# ProDuino-v2.net
KiCad netlist of a schematic drawn in EAGLE
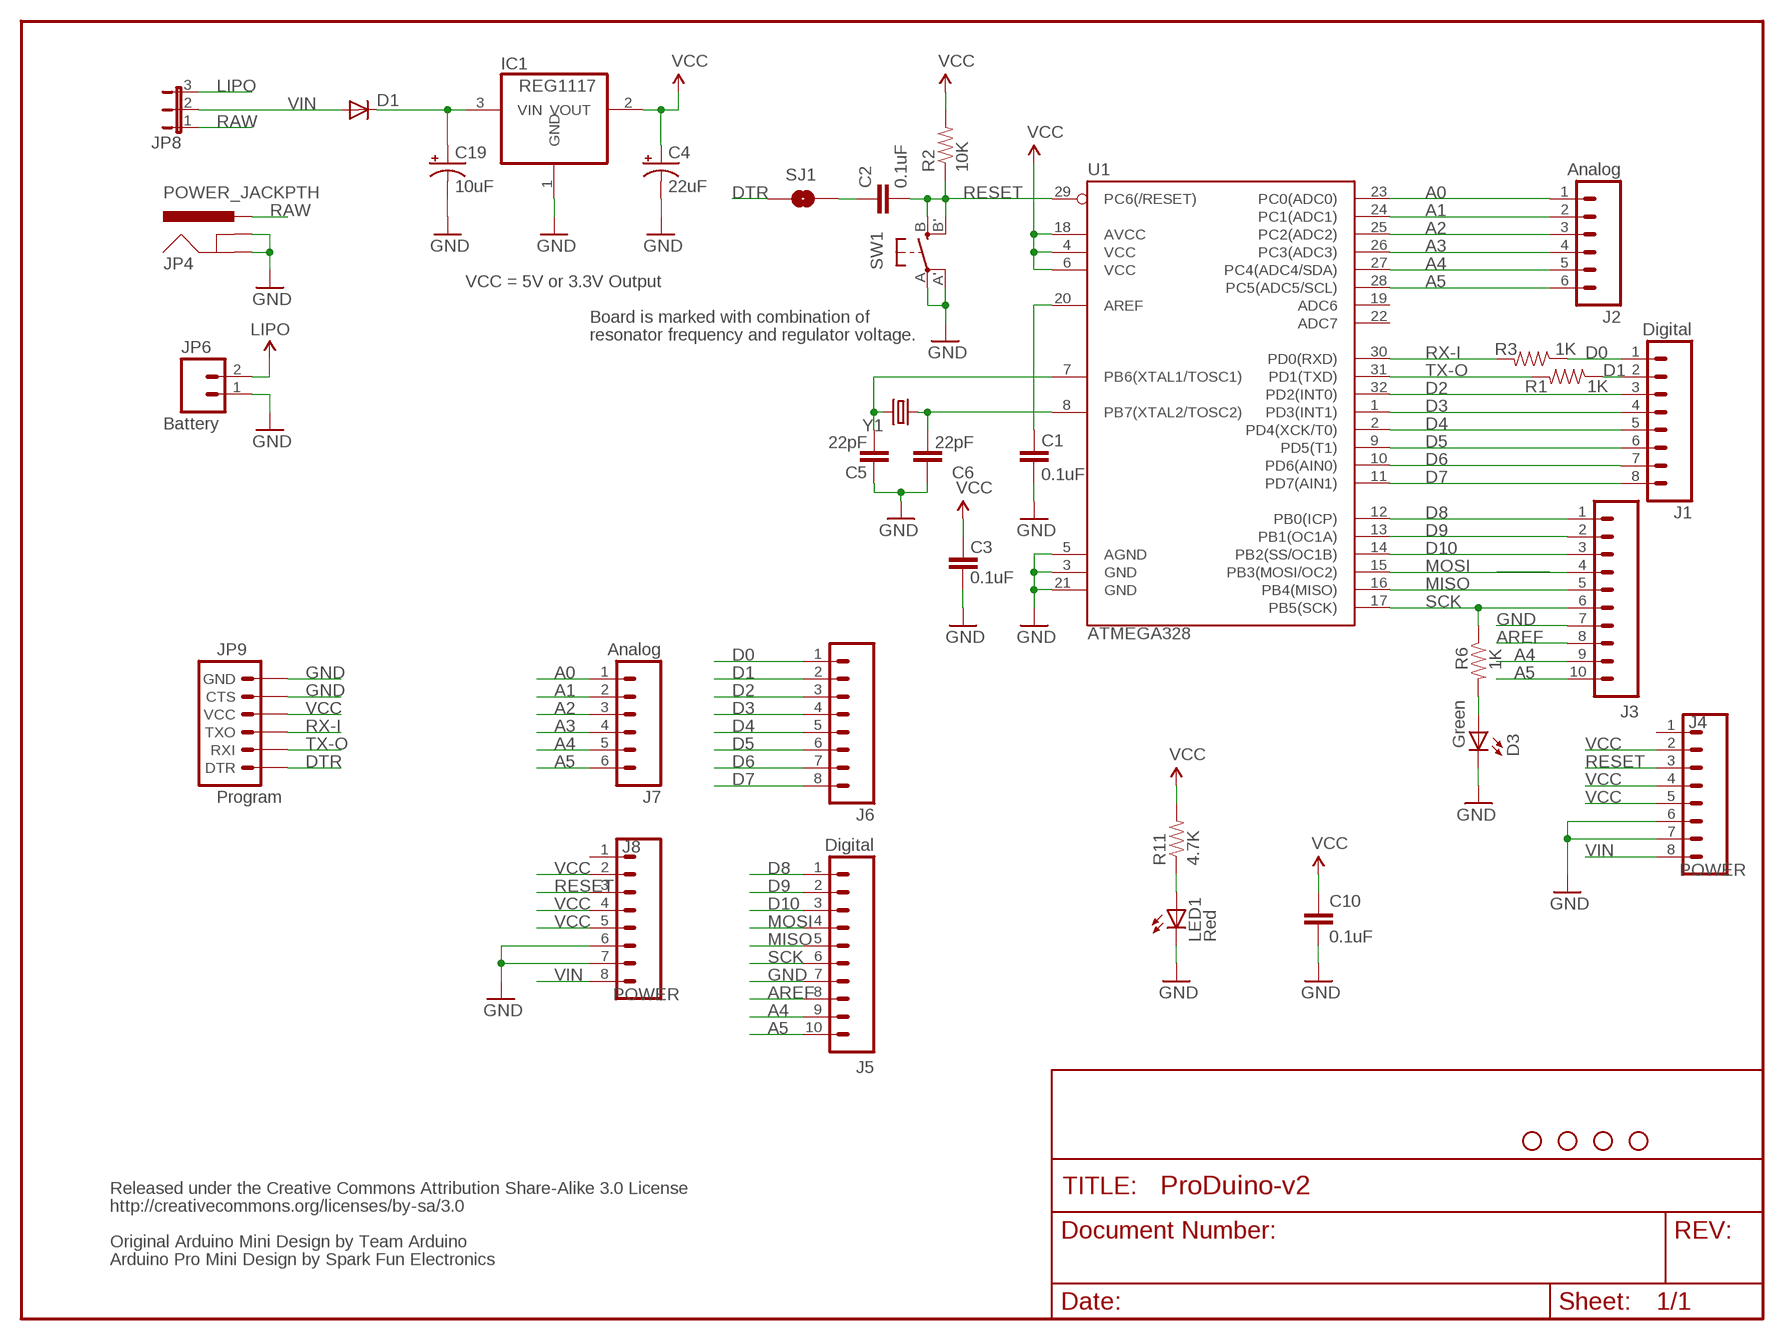
[diagram p0: schematic, sheet 1]

(export (version "E")
  (design (tool "Eeschema 10.0.6"))
  (components
    (comp (ref "C1")
      (value "0.1uF")
      (footprint "eagle-import:0603-CAP")
      (libsource (lib "eagle-import") (part "CAP0603-CAP"))
    )
    (comp (ref "C2")
      (value "0.1uF")
      (footprint "eagle-import:0603-CAP")
      (libsource (lib "eagle-import") (part "CAP0603-CAP"))
    )
    (comp (ref "C3")
      (value "0.1uF")
      (footprint "eagle-import:0603-CAP")
      (libsource (lib "eagle-import") (part "CAP0603-CAP"))
    )
    (comp (ref "C4")
      (value "22uF")
      (footprint "eagle-import:EIA3216")
      (libsource (lib "eagle-import") (part "CAP_POL1206"))
    )
    (comp (ref "C5")
      (value "22pF")
      (footprint "eagle-import:0603-CAP")
      (libsource (lib "eagle-import") (part "CAP0603-CAP"))
    )
    (comp (ref "C6")
      (value "22pF")
      (footprint "eagle-import:0603-CAP")
      (libsource (lib "eagle-import") (part "CAP0603-CAP"))
    )
    (comp (ref "C10")
      (value "0.1uF")
      (footprint "eagle-import:0603-CAP")
      (libsource (lib "eagle-import") (part "CAP0603-CAP"))
    )
    (comp (ref "C19")
      (value "10uF")
      (footprint "eagle-import:EIA3216")
      (libsource (lib "eagle-import") (part "CAP_POL1206"))
    )
    (comp (ref "D1")
      (value "DIODESMA")
      (footprint "eagle-import:SMA-DIODE")
      (libsource (lib "eagle-import") (part "DIODESMA"))
    )
    (comp (ref "D3")
      (value "Green")
      (footprint "eagle-import:LED-0603")
      (libsource (lib "eagle-import") (part "LED0603"))
    )
    (comp (ref "IC1")
      (value "REG1117")
      (footprint "eagle-import:SOT223")
      (libsource (lib "eagle-import") (part "REG1117"))
    )
    (comp (ref "J1")
      (value "Digital")
      (footprint "eagle-import:1X08")
      (libsource (lib "eagle-import") (part "M081X08"))
    )
    (comp (ref "J2")
      (value "Analog")
      (footprint "eagle-import:1X06")
      (libsource (lib "eagle-import") (part "M06SIP"))
    )
    (comp (ref "J3")
      (value "M10\"")
      (footprint "eagle-import:1X10")
      (libsource (lib "eagle-import") (part "M10{dblquote}"))
    )
    (comp (ref "J4")
      (value "POWER")
      (footprint "eagle-import:1X08")
      (libsource (lib "eagle-import") (part "SparkFun-Connectors_M081X08"))
    )
    (comp (ref "J5")
      (value "Digital")
      (footprint "eagle-import:1X10")
      (libsource (lib "eagle-import") (part "M10{dblquote}"))
    )
    (comp (ref "J6")
      (value "M081X08")
      (footprint "eagle-import:1X08")
      (libsource (lib "eagle-import") (part "M081X08"))
    )
    (comp (ref "J7")
      (value "Analog")
      (footprint "eagle-import:1X06")
      (libsource (lib "eagle-import") (part "M06SIP"))
    )
    (comp (ref "J8")
      (value "POWER")
      (footprint "eagle-import:1X08")
      (libsource (lib "eagle-import") (part "SparkFun-Connectors_M081X08"))
    )
    (comp (ref "JP4")
      (value "POWER_JACKPTH")
      (footprint "eagle-import:POWER_JACK_PTH")
      (libsource (lib "eagle-import") (part "POWER_JACKPTH"))
    )
    (comp (ref "JP6")
      (value "Battery")
      (footprint "eagle-import:1X02")
      (libsource (lib "eagle-import") (part "M02PTH"))
    )
    (comp (ref "JP8")
      (value "JP2E")
      (footprint "eagle-import:JP2")
      (libsource (lib "eagle-import") (part "JP2E"))
    )
    (comp (ref "JP9")
      (value "Program")
      (footprint "eagle-import:1X06")
      (libsource (lib "eagle-import") (part "ARDUINO_SERIAL_PROGRAMPTH"))
    )
    (comp (ref "LED1")
      (value "Red")
      (footprint "eagle-import:LED-0603")
      (libsource (lib "eagle-import") (part "LED0603"))
    )
    (comp (ref "R1")
      (value "1K")
      (footprint "eagle-import:0603-RES")
      (libsource (lib "eagle-import") (part "RESISTOR0603-RES"))
    )
    (comp (ref "R2")
      (value "10K")
      (footprint "eagle-import:0603-RES")
      (libsource (lib "eagle-import") (part "RESISTOR0603-RES"))
    )
    (comp (ref "R3")
      (value "1K")
      (footprint "eagle-import:0603-RES")
      (libsource (lib "eagle-import") (part "RESISTOR0603-RES"))
    )
    (comp (ref "R6")
      (value "1K")
      (footprint "eagle-import:0603-RES")
      (libsource (lib "eagle-import") (part "RESISTOR0603-RES"))
    )
    (comp (ref "R11")
      (value "4.7K")
      (footprint "eagle-import:0603-RES")
      (libsource (lib "eagle-import") (part "RESISTOR0603-RES"))
    )
    (comp (ref "SJ1")
      (value "SOLDERJUMPERNC3")
      (footprint "eagle-import:SJ_2S-NOTRACE")
      (libsource (lib "eagle-import") (part "SOLDERJUMPERNC2"))
    )
    (comp (ref "SW1")
      (value "SPST_TACT-EVQQ2")
      (footprint "eagle-import:EVQ-Q2")
      (libsource (lib "eagle-import") (part "SPST_TACT-EVQQ2"))
    )
    (comp (ref "U$1")
      (value "STAND-OFF")
      (footprint "eagle-import:STAND-OFF")
      (libsource (lib "eagle-import") (part "STAND-OFF"))
    )
    (comp (ref "U$3")
      (value "STAND-OFF")
      (footprint "eagle-import:STAND-OFF")
      (libsource (lib "eagle-import") (part "STAND-OFF"))
    )
    (comp (ref "U$9")
      (value "STAND-OFF")
      (footprint "eagle-import:STAND-OFF")
      (libsource (lib "eagle-import") (part "STAND-OFF"))
    )
    (comp (ref "U$10")
      (value "STAND-OFF")
      (footprint "eagle-import:STAND-OFF")
      (libsource (lib "eagle-import") (part "STAND-OFF"))
    )
    (comp (ref "U1")
      (value "ATMEGA328")
      (footprint "eagle-import:TQFP32-08")
      (libsource (lib "eagle-import") (part "ATMEGA168"))
    )
    (comp (ref "Y1")
      (value "CRYSTAL5X3")
      (footprint "eagle-import:CRYSTAL-SMD-5X3")
      (libsource (lib "eagle-import") (part "CRYSTAL5X3"))
    )
  )
  (nets
    (net (code "1") (name "/A0") (class "Default")
      (node (ref "J2") (pin "1") (pinfunction "1_1") (pintype "passive"))
      (node (ref "J7") (pin "1") (pinfunction "1_1") (pintype "passive"))
      (node (ref "U1") (pin "23") (pinfunction "PC0(ADC0)_23") (pintype "bidirectional"))
    )
    (net (code "2") (name "/A1") (class "Default")
      (node (ref "J2") (pin "2") (pinfunction "2_2") (pintype "passive"))
      (node (ref "J7") (pin "2") (pinfunction "2_2") (pintype "passive"))
      (node (ref "U1") (pin "24") (pinfunction "PC1(ADC1)_24") (pintype "bidirectional"))
    )
    (net (code "3") (name "/A2") (class "Default")
      (node (ref "J2") (pin "3") (pinfunction "3_3") (pintype "passive"))
      (node (ref "J7") (pin "3") (pinfunction "3_3") (pintype "passive"))
      (node (ref "U1") (pin "25") (pinfunction "PC2(ADC2)_25") (pintype "bidirectional"))
    )
    (net (code "4") (name "/A3") (class "Default")
      (node (ref "J2") (pin "4") (pinfunction "4_4") (pintype "passive"))
      (node (ref "J7") (pin "4") (pinfunction "4_4") (pintype "passive"))
      (node (ref "U1") (pin "26") (pinfunction "PC3(ADC3)_26") (pintype "bidirectional"))
    )
    (net (code "5") (name "/A4") (class "Default")
      (node (ref "J2") (pin "5") (pinfunction "5_5") (pintype "passive"))
      (node (ref "J3") (pin "9") (pinfunction "9_9") (pintype "passive"))
      (node (ref "J5") (pin "9") (pinfunction "9_9") (pintype "passive"))
      (node (ref "J7") (pin "5") (pinfunction "5_5") (pintype "passive"))
      (node (ref "U1") (pin "27") (pinfunction "PC4(ADC4/SDA)_27") (pintype "bidirectional"))
    )
    (net (code "6") (name "/A5") (class "Default")
      (node (ref "J2") (pin "6") (pinfunction "6_6") (pintype "passive"))
      (node (ref "J3") (pin "10") (pinfunction "10_10") (pintype "passive"))
      (node (ref "J5") (pin "10") (pinfunction "10_10") (pintype "passive"))
      (node (ref "J7") (pin "6") (pinfunction "6_6") (pintype "passive"))
      (node (ref "U1") (pin "28") (pinfunction "PC5(ADC5/SCL)_28") (pintype "bidirectional"))
    )
    (net (code "7") (name "/AREF") (class "Default")
      (node (ref "C1") (pin "2") (pinfunction "2_2") (pintype "passive"))
      (node (ref "J3") (pin "8") (pinfunction "8_8") (pintype "passive"))
      (node (ref "J5") (pin "8") (pinfunction "8_8") (pintype "passive"))
      (node (ref "U1") (pin "20") (pinfunction "AREF_20") (pintype "bidirectional"))
    )
    (net (code "8") (name "/D0") (class "Default")
      (node (ref "J1") (pin "1") (pinfunction "1_1") (pintype "passive"))
      (node (ref "J6") (pin "1") (pinfunction "1_1") (pintype "passive"))
      (node (ref "R3") (pin "1") (pinfunction "1_1") (pintype "passive"))
    )
    (net (code "9") (name "/D1") (class "Default")
      (node (ref "J1") (pin "2") (pinfunction "2_2") (pintype "passive"))
      (node (ref "J6") (pin "2") (pinfunction "2_2") (pintype "passive"))
      (node (ref "R1") (pin "1") (pinfunction "1_1") (pintype "passive"))
    )
    (net (code "10") (name "/D2") (class "Default")
      (node (ref "J1") (pin "3") (pinfunction "3_3") (pintype "passive"))
      (node (ref "J6") (pin "3") (pinfunction "3_3") (pintype "passive"))
      (node (ref "U1") (pin "32") (pinfunction "PD2(INT0)_32") (pintype "bidirectional"))
    )
    (net (code "11") (name "/D3") (class "Default")
      (node (ref "J1") (pin "4") (pinfunction "4_4") (pintype "passive"))
      (node (ref "J6") (pin "4") (pinfunction "4_4") (pintype "passive"))
      (node (ref "U1") (pin "1") (pinfunction "PD3(INT1)_1") (pintype "bidirectional"))
    )
    (net (code "12") (name "/D4") (class "Default")
      (node (ref "J1") (pin "5") (pinfunction "5_5") (pintype "passive"))
      (node (ref "J6") (pin "5") (pinfunction "5_5") (pintype "passive"))
      (node (ref "U1") (pin "2") (pinfunction "PD4(XCK/T0)_2") (pintype "bidirectional"))
    )
    (net (code "13") (name "/D5") (class "Default")
      (node (ref "J1") (pin "6") (pinfunction "6_6") (pintype "passive"))
      (node (ref "J6") (pin "6") (pinfunction "6_6") (pintype "passive"))
      (node (ref "U1") (pin "9") (pinfunction "PD5(T1)_9") (pintype "bidirectional"))
    )
    (net (code "14") (name "/D6") (class "Default")
      (node (ref "J1") (pin "7") (pinfunction "7_7") (pintype "passive"))
      (node (ref "J6") (pin "7") (pinfunction "7_7") (pintype "passive"))
      (node (ref "U1") (pin "10") (pinfunction "PD6(AIN0)_10") (pintype "bidirectional"))
    )
    (net (code "15") (name "/D7") (class "Default")
      (node (ref "J1") (pin "8") (pinfunction "8_8") (pintype "passive"))
      (node (ref "J6") (pin "8") (pinfunction "8_8") (pintype "passive"))
      (node (ref "U1") (pin "11") (pinfunction "PD7(AIN1)_11") (pintype "bidirectional"))
    )
    (net (code "16") (name "/D8") (class "Default")
      (node (ref "J3") (pin "1") (pinfunction "1_1") (pintype "passive"))
      (node (ref "J5") (pin "1") (pinfunction "1_1") (pintype "passive"))
      (node (ref "U1") (pin "12") (pinfunction "PB0(ICP)_12") (pintype "bidirectional"))
    )
    (net (code "17") (name "/D9") (class "Default")
      (node (ref "J3") (pin "2") (pinfunction "2_2") (pintype "passive"))
      (node (ref "J5") (pin "2") (pinfunction "2_2") (pintype "passive"))
      (node (ref "U1") (pin "13") (pinfunction "PB1(OC1A)_13") (pintype "bidirectional"))
    )
    (net (code "18") (name "/D10") (class "Default")
      (node (ref "J3") (pin "3") (pinfunction "3_3") (pintype "passive"))
      (node (ref "J5") (pin "3") (pinfunction "3_3") (pintype "passive"))
      (node (ref "U1") (pin "14") (pinfunction "PB2(SS/OC1B)_14") (pintype "bidirectional"))
    )
    (net (code "19") (name "/DTR") (class "Default")
      (node (ref "JP9") (pin "1") (pinfunction "DTR_1") (pintype "passive"))
      (node (ref "SJ1") (pin "1") (pinfunction "1_1") (pintype "passive"))
    )
    (net (code "20") (name "/MISO") (class "Default")
      (node (ref "J3") (pin "5") (pinfunction "5_5") (pintype "passive"))
      (node (ref "J5") (pin "5") (pinfunction "5_5") (pintype "passive"))
      (node (ref "U1") (pin "16") (pinfunction "PB4(MISO)_16") (pintype "bidirectional"))
    )
    (net (code "21") (name "/MOSI") (class "Default")
      (node (ref "J3") (pin "4") (pinfunction "4_4") (pintype "passive"))
      (node (ref "J5") (pin "4") (pinfunction "4_4") (pintype "passive"))
      (node (ref "U1") (pin "15") (pinfunction "PB3(MOSI/OC2)_15") (pintype "bidirectional"))
    )
    (net (code "22") (name "/RAW") (class "Default")
      (node (ref "JP4") (pin "PWR") (pinfunction "PWR_PWR") (pintype "bidirectional"))
      (node (ref "JP8") (pin "1") (pinfunction "1_1") (pintype "passive"))
    )
    (net (code "23") (name "/RESET") (class "Default")
      (node (ref "C2") (pin "2") (pinfunction "2_2") (pintype "passive"))
      (node (ref "J4") (pin "3") (pinfunction "3_3") (pintype "passive"))
      (node (ref "J8") (pin "3") (pinfunction "3_3") (pintype "passive"))
      (node (ref "R2") (pin "1") (pinfunction "1_1") (pintype "passive"))
      (node (ref "SW1") (pin "B") (pinfunction "S_B") (pintype "passive"))
      (node (ref "SW1") (pin "B'") (pinfunction "S1_B'") (pintype "passive"))
      (node (ref "U1") (pin "29") (pinfunction "PC6(/RESET)_29") (pintype "bidirectional"))
    )
    (net (code "24") (name "/RX-I") (class "Default")
      (node (ref "JP9") (pin "3") (pinfunction "TXO_3") (pintype "passive"))
      (node (ref "R3") (pin "2") (pinfunction "2_2") (pintype "passive"))
      (node (ref "U1") (pin "30") (pinfunction "PD0(RXD)_30") (pintype "bidirectional"))
    )
    (net (code "25") (name "/SCK") (class "Default")
      (node (ref "J3") (pin "6") (pinfunction "6_6") (pintype "passive"))
      (node (ref "J5") (pin "6") (pinfunction "6_6") (pintype "passive"))
      (node (ref "R6") (pin "1") (pinfunction "1_1") (pintype "passive"))
      (node (ref "U1") (pin "17") (pinfunction "PB5(SCK)_17") (pintype "bidirectional"))
    )
    (net (code "26") (name "/TX-O") (class "Default")
      (node (ref "JP9") (pin "2") (pinfunction "RXI_2") (pintype "passive"))
      (node (ref "R1") (pin "2") (pinfunction "2_2") (pintype "passive"))
      (node (ref "U1") (pin "31") (pinfunction "PD1(TXD)_31") (pintype "bidirectional"))
    )
    (net (code "27") (name "/VIN") (class "Default")
      (node (ref "D1") (pin "A") (pinfunction "A_A") (pintype "passive"))
      (node (ref "J4") (pin "8") (pinfunction "8_8") (pintype "passive"))
      (node (ref "J8") (pin "8") (pinfunction "8_8") (pintype "passive"))
      (node (ref "JP8") (pin "2") (pinfunction "2_2") (pintype "passive"))
    )
    (net (code "28") (name "GND") (class "Default")
      (node (ref "C1") (pin "1") (pinfunction "1_1") (pintype "passive"))
      (node (ref "C10") (pin "2") (pinfunction "2_2") (pintype "passive"))
      (node (ref "C19") (pin "C") (pinfunction "-_C") (pintype "passive"))
      (node (ref "C3") (pin "1") (pinfunction "1_1") (pintype "passive"))
      (node (ref "C4") (pin "C") (pinfunction "-_C") (pintype "passive"))
      (node (ref "C5") (pin "2") (pinfunction "2_2") (pintype "passive"))
      (node (ref "C6") (pin "2") (pinfunction "2_2") (pintype "passive"))
      (node (ref "D3") (pin "C") (pinfunction "C_C") (pintype "passive"))
      (node (ref "IC1") (pin "1") (pinfunction "GND_1") (pintype "power_in"))
      (node (ref "J3") (pin "7") (pinfunction "7_7") (pintype "passive"))
      (node (ref "J4") (pin "6") (pinfunction "6_6") (pintype "passive"))
      (node (ref "J4") (pin "7") (pinfunction "7_7") (pintype "passive"))
      (node (ref "J5") (pin "7") (pinfunction "7_7") (pintype "passive"))
      (node (ref "J8") (pin "6") (pinfunction "6_6") (pintype "passive"))
      (node (ref "J8") (pin "7") (pinfunction "7_7") (pintype "passive"))
      (node (ref "JP4") (pin "GND") (pinfunction "GND_GND") (pintype "bidirectional"))
      (node (ref "JP4") (pin "GNDBREAK") (pinfunction "GNDBREAK_GNDBREAK") (pintype "bidirectional"))
      (node (ref "JP6") (pin "1") (pinfunction "1_1") (pintype "passive"))
      (node (ref "JP9") (pin "5") (pinfunction "CTS_5") (pintype "passive"))
      (node (ref "JP9") (pin "6") (pinfunction "GND_6") (pintype "passive"))
      (node (ref "LED1") (pin "C") (pinfunction "C_C") (pintype "passive"))
      (node (ref "SW1") (pin "A") (pinfunction "P_A") (pintype "passive"))
      (node (ref "SW1") (pin "A'") (pinfunction "P1_A'") (pintype "passive"))
      (node (ref "U1") (pin "21") (pinfunction "GND_21") (pintype "bidirectional"))
      (node (ref "U1") (pin "3") (pinfunction "GND_3") (pintype "bidirectional"))
      (node (ref "U1") (pin "5") (pinfunction "AGND_5") (pintype "bidirectional"))
    )
    (net (code "29") (name "LIPO") (class "Default")
      (node (ref "JP6") (pin "2") (pinfunction "2_2") (pintype "passive"))
      (node (ref "JP8") (pin "3") (pinfunction "3_3") (pintype "passive"))
    )
    (net (code "30") (name "Net-(C2-Pad1)") (class "Default")
      (node (ref "C2") (pin "1") (pinfunction "1_1") (pintype "passive"))
      (node (ref "SJ1") (pin "2") (pinfunction "2_2") (pintype "passive"))
    )
    (net (code "31") (name "Net-(C19-+)") (class "Default")
      (node (ref "C19") (pin "A") (pinfunction "+_A") (pintype "passive"))
      (node (ref "D1") (pin "C") (pinfunction "C_C") (pintype "passive"))
      (node (ref "IC1") (pin "3") (pinfunction "VIN_3") (pintype "input"))
    )
    (net (code "32") (name "Net-(D3-PadA)") (class "Default")
      (node (ref "D3") (pin "A") (pinfunction "A_A") (pintype "passive"))
      (node (ref "R6") (pin "2") (pinfunction "2_2") (pintype "passive"))
    )
    (net (code "33") (name "Net-(LED1-PadA)") (class "Default")
      (node (ref "LED1") (pin "A") (pinfunction "A_A") (pintype "passive"))
      (node (ref "R11") (pin "1") (pinfunction "1_1") (pintype "passive"))
    )
    (net (code "34") (name "Net-(U1-PB6(XTAL1{slash}TOSC1))") (class "Default")
      (node (ref "C5") (pin "1") (pinfunction "1_1") (pintype "passive"))
      (node (ref "U1") (pin "7") (pinfunction "PB6(XTAL1/TOSC1)_7") (pintype "bidirectional"))
      (node (ref "Y1") (pin "3") (pinfunction "2_3") (pintype "passive"))
    )
    (net (code "35") (name "Net-(U1-PB7(XTAL2{slash}TOSC2))") (class "Default")
      (node (ref "C6") (pin "1") (pinfunction "1_1") (pintype "passive"))
      (node (ref "U1") (pin "8") (pinfunction "PB7(XTAL2/TOSC2)_8") (pintype "bidirectional"))
      (node (ref "Y1") (pin "1") (pinfunction "1_1") (pintype "passive"))
    )
    (net (code "36") (name "VCC") (class "Default")
      (node (ref "C10") (pin "1") (pinfunction "1_1") (pintype "passive"))
      (node (ref "C3") (pin "2") (pinfunction "2_2") (pintype "passive"))
      (node (ref "C4") (pin "A") (pinfunction "+_A") (pintype "passive"))
      (node (ref "IC1") (pin "2") (pinfunction "VOUT_2") (pintype "output"))
      (node (ref "J4") (pin "2") (pinfunction "2_2") (pintype "passive"))
      (node (ref "J4") (pin "4") (pinfunction "4_4") (pintype "passive"))
      (node (ref "J4") (pin "5") (pinfunction "5_5") (pintype "passive"))
      (node (ref "J8") (pin "2") (pinfunction "2_2") (pintype "passive"))
      (node (ref "J8") (pin "4") (pinfunction "4_4") (pintype "passive"))
      (node (ref "J8") (pin "5") (pinfunction "5_5") (pintype "passive"))
      (node (ref "JP9") (pin "4") (pinfunction "VCC_4") (pintype "passive"))
      (node (ref "R11") (pin "2") (pinfunction "2_2") (pintype "passive"))
      (node (ref "R2") (pin "2") (pinfunction "2_2") (pintype "passive"))
      (node (ref "U1") (pin "18") (pinfunction "AVCC_18") (pintype "bidirectional"))
      (node (ref "U1") (pin "4") (pinfunction "VCC_4") (pintype "bidirectional"))
      (node (ref "U1") (pin "6") (pinfunction "VCC_6") (pintype "bidirectional"))
    )
    (net (code "37") (name "unconnected-(J4-Pad1)") (class "Default")
      (node (ref "J4") (pin "1") (pinfunction "1_1") (pintype "passive"))
    )
    (net (code "38") (name "unconnected-(J8-Pad1)") (class "Default")
      (node (ref "J8") (pin "1") (pinfunction "1_1") (pintype "passive"))
    )
    (net (code "39") (name "unconnected-(U1-ADC6-Pad19)") (class "Default")
      (node (ref "U1") (pin "19") (pinfunction "ADC6_19") (pintype "bidirectional"))
    )
    (net (code "40") (name "unconnected-(U1-ADC7-Pad22)") (class "Default")
      (node (ref "U1") (pin "22") (pinfunction "ADC7_22") (pintype "bidirectional"))
    )
  )
)
